# STM32.net
KiCad netlist of a schematic drawn in Altium Designer
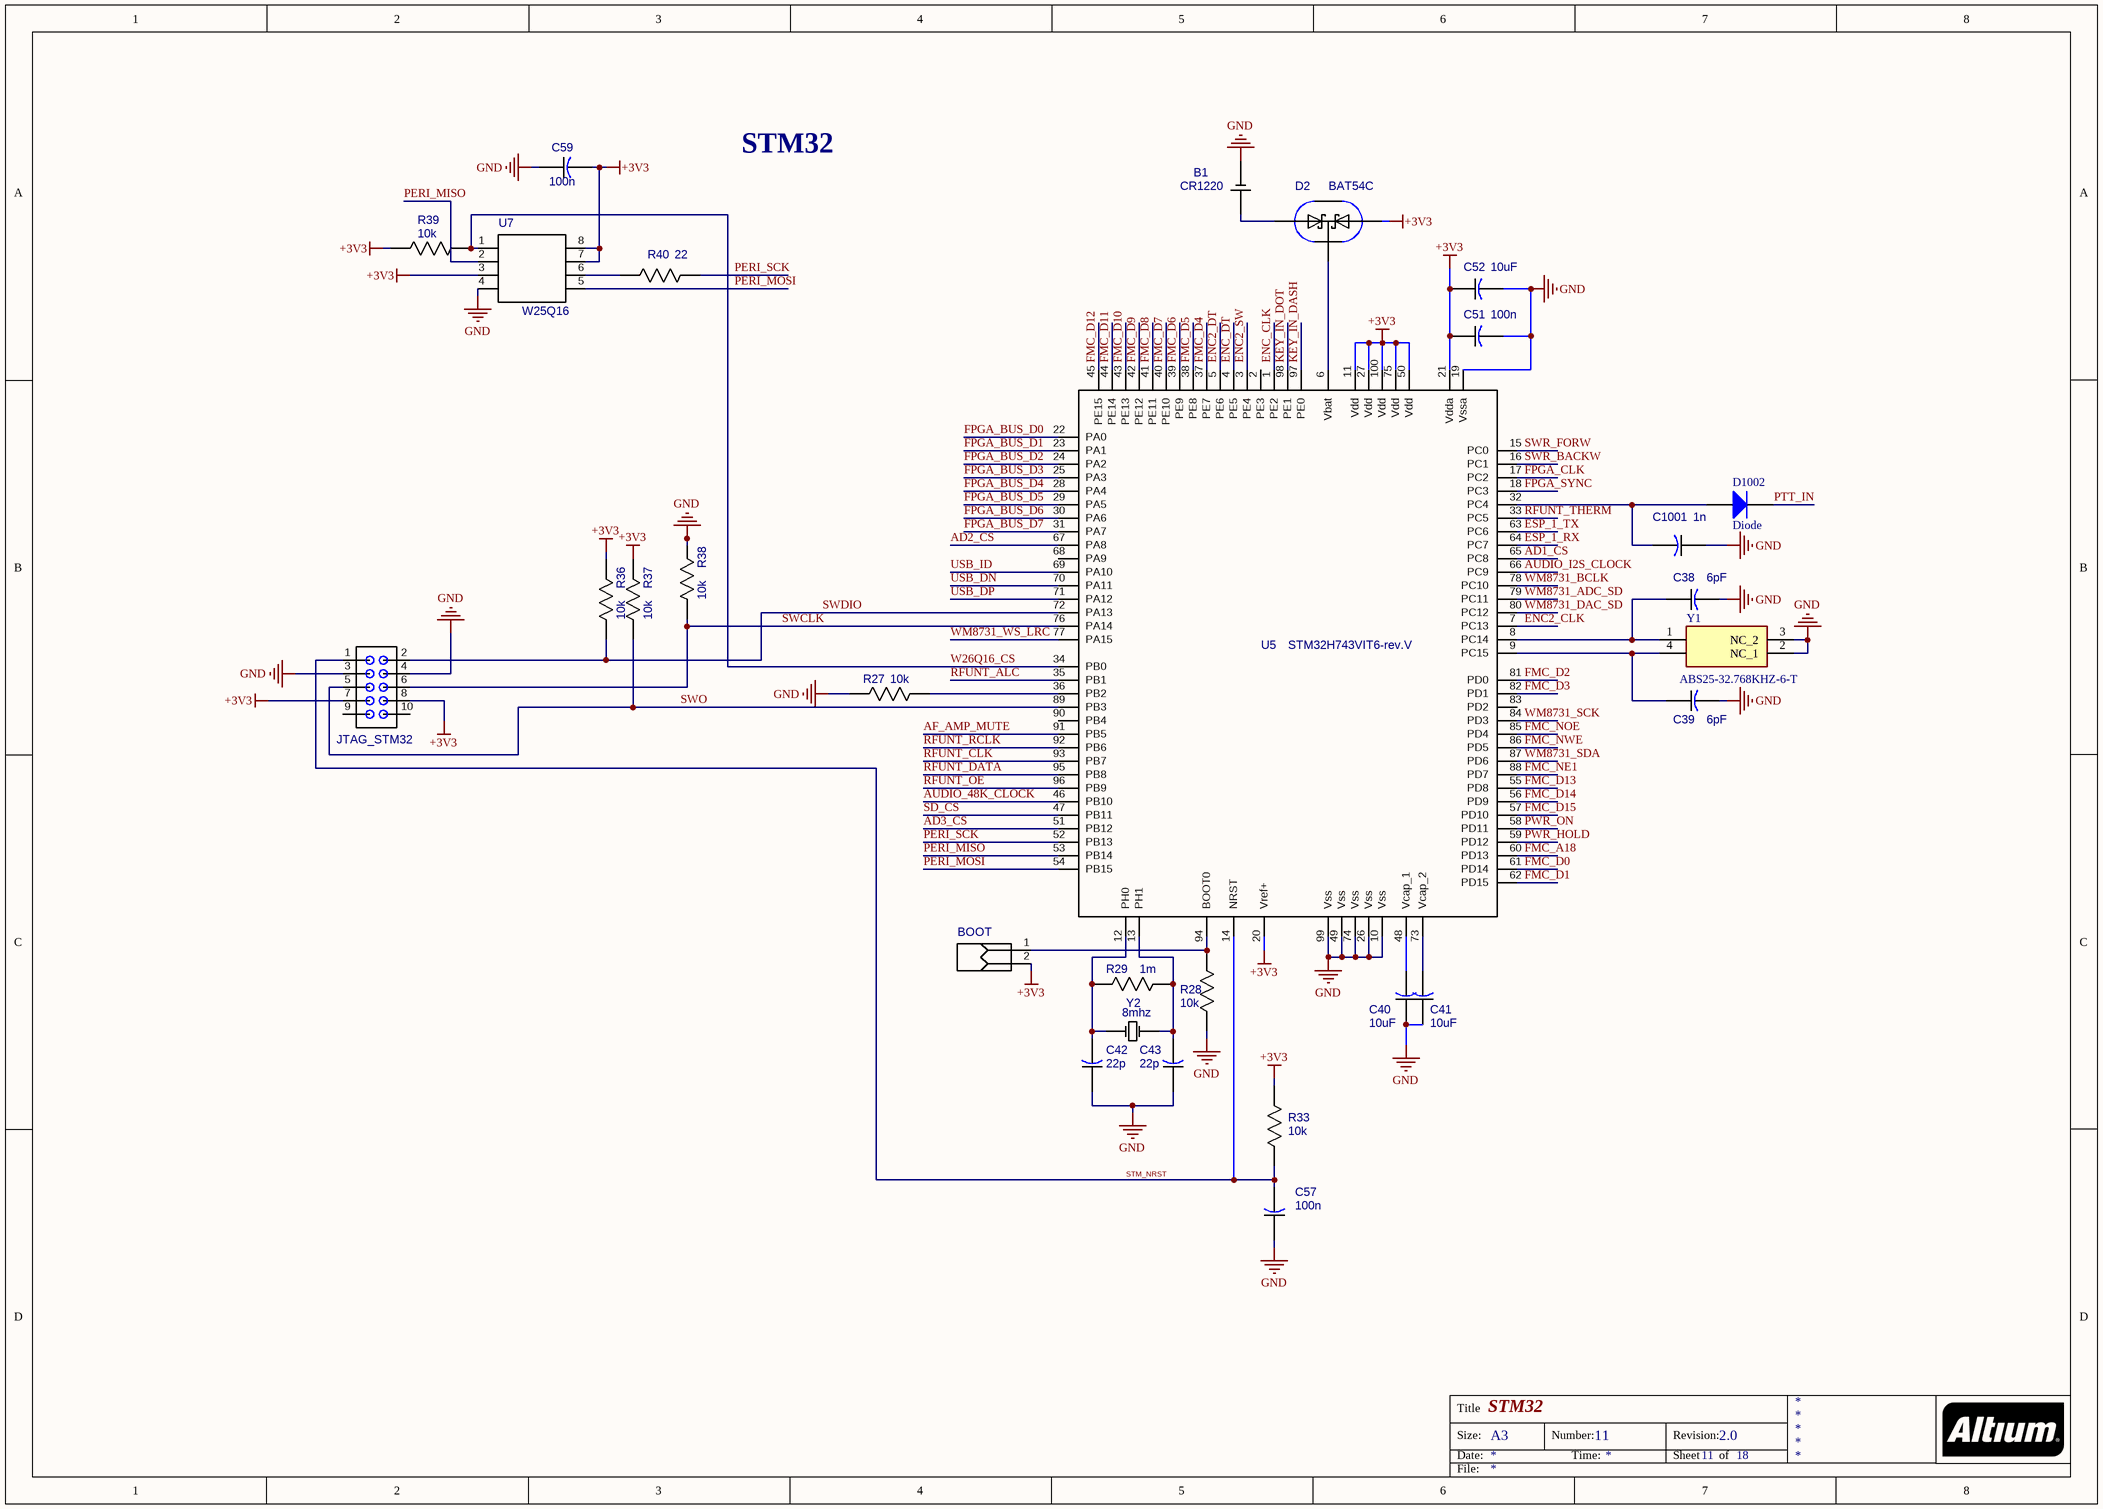
[diagram p0: STM32.SchDoc]

(export (version "E")
  (design (tool "Eeschema 10.0.6"))
  (components
    (comp (ref "B1")
      (value "CR1220")
      (footprint "KLS5-CR1220-01")
      (description "BR1632A/FA")
      (fields (field (name "Comment") "CR1220 +"))
      (libsource (lib "*") (part "BR1632A/FA"))
    )
    (comp (ref "BOOT")
      (value "~")
      (footprint "51022-0200")
      (description "2 Pin")
      (libsource (lib "*") (part "51022-0200"))
    )
    (comp (ref "C38")
      (value "6pF")
      (footprint "CAP_0805")
      (description "CAP_0805")
      (libsource (lib "*") (part "CAP_0805"))
    )
    (comp (ref "C39")
      (value "6pF")
      (footprint "CAP_0805")
      (description "CAP_0805")
      (libsource (lib "*") (part "CAP_0805"))
    )
    (comp (ref "C40")
      (value "10uF")
      (footprint "CAP_0805")
      (description "CAP_0805")
      (libsource (lib "*") (part "CAP_0805"))
    )
    (comp (ref "C41")
      (value "10uF")
      (footprint "CAP_0805")
      (description "CAP_0805")
      (libsource (lib "*") (part "CAP_0805"))
    )
    (comp (ref "C42")
      (value "22p")
      (footprint "CAP_0805")
      (description "CAP_0805")
      (libsource (lib "*") (part "CAP_0805"))
    )
    (comp (ref "C43")
      (value "22p")
      (footprint "CAP_0805")
      (description "CAP_0805")
      (libsource (lib "*") (part "CAP_0805"))
    )
    (comp (ref "C51")
      (value "100n")
      (footprint "CAP_0805")
      (description "CAP_0805")
      (libsource (lib "*") (part "CAP_0805"))
    )
    (comp (ref "C52")
      (value "10uF")
      (footprint "CAP_0805")
      (description "CAP_0805")
      (libsource (lib "*") (part "CAP_0805"))
    )
    (comp (ref "C57")
      (value "100n")
      (footprint "CAP_0805")
      (description "CAP_0805")
      (libsource (lib "*") (part "CAP_0805"))
    )
    (comp (ref "C59")
      (value "100n")
      (footprint "CAP_0805")
      (description "CAP_0805")
      (libsource (lib "*") (part "CAP_0805"))
    )
    (comp (ref "C1001")
      (value "1n")
      (footprint "CAP_0805")
      (description "CAP_0805")
      (fields (field (name "Comment") "100n"))
      (libsource (lib "*") (part "CAP_0805"))
    )
    (comp (ref "D2") (value "BAT54C") (footprint "BAT54C") (libsource (lib "*") (part "BAT54C")))
    (comp (ref "D1002")
      (value "Diode")
      (footprint "C1206")
      (description "Default Diode")
      (fields (field (name "PUBLISHER") "Altium Limited"))
      (libsource (lib "Miscellaneous Devices") (part "Diode"))
    )
    (comp (ref "JTAG_STM32")
      (value "~")
      (footprint "IDC10")
      (description "2*5 Pin")
      (libsource (lib "*") (part "IDC10"))
    )
    (comp (ref "R27")
      (value "10k")
      (footprint "RES_0805")
      (description "RES_0805")
      (libsource (lib "*") (part "RES_0805"))
    )
    (comp (ref "R28")
      (value "10k")
      (footprint "RES_0805")
      (description "RES_0805")
      (libsource (lib "*") (part "RES_0805"))
    )
    (comp (ref "R29")
      (value "1m")
      (footprint "RES_0805")
      (description "RES_0805")
      (libsource (lib "*") (part "RES_0805"))
    )
    (comp (ref "R33")
      (value "10k")
      (footprint "RES_0805")
      (description "RES_0805")
      (libsource (lib "*") (part "RES_0805"))
    )
    (comp (ref "R36")
      (value "10k")
      (footprint "RES_0805")
      (description "RES_0805")
      (libsource (lib "*") (part "RES_0805"))
    )
    (comp (ref "R37")
      (value "10k")
      (footprint "RES_0805")
      (description "RES_0805")
      (libsource (lib "*") (part "RES_0805"))
    )
    (comp (ref "R38")
      (value "10k")
      (footprint "RES_0805")
      (description "RES_0805")
      (libsource (lib "*") (part "RES_0805"))
    )
    (comp (ref "R39")
      (value "10k")
      (footprint "RES_0805")
      (description "RES_0805")
      (libsource (lib "*") (part "RES_0805"))
    )
    (comp (ref "R40")
      (value "22")
      (footprint "RES_0805")
      (description "RES_0805")
      (libsource (lib "*") (part "RES_0805"))
    )
    (comp (ref "U5")
      (value "STM32H743VIT6-rev.V")
      (footprint "STM32H743VIT6")
      (description "STM32H743VIT6")
      (libsource (lib "*") (part "STM32H743VIT6"))
    )
    (comp (ref "U7") (value "W25Q16") (footprint "W25Q16") (libsource (lib "*") (part "W25Q16")))
    (comp (ref "Y1")
      (value "ABS25-32.768KHZ-6-T")
      (footprint "SamacSys:ABS25")
      (description "Crystal or Oscillator")
      (fields
        (field (name "MOUSER PART NUMBER") "815-ABS25-32.768K6-T")
        (field (name "RS PART NUMBER") "1712795P")
      )
      (libsource (lib "*") (part "ABS25-32.768KHZ-6-T"))
    )
    (comp (ref "Y2")
      (value "8mhz")
      (footprint "ECS-200-20-1")
      (description "ECS-200-20-1")
      (libsource (lib "*") (part "ECS-200-20-1"))
    )
  )
  (nets
    (net (code "1") (name "+3V3") (class "Default")
      (node (ref "BOOT") (pin "2") (pinfunction "2_2") (pintype "passive"))
      (node (ref "C51") (pin "1") (pinfunction "1_1") (pintype "passive"))
      (node (ref "C52") (pin "1") (pinfunction "1_1") (pintype "passive"))
      (node (ref "C59") (pin "2") (pinfunction "2_2") (pintype "passive"))
      (node (ref "D2") (pin "1") (pinfunction "(A1)_1") (pintype "passive"))
      (node (ref "JTAG_STM32") (pin "7") (pinfunction "7_7") (pintype "passive"))
      (node (ref "JTAG_STM32") (pin "8") (pinfunction "8_8") (pintype "passive"))
      (node (ref "R33") (pin "2") (pinfunction "2_2") (pintype "passive"))
      (node (ref "R36") (pin "1") (pinfunction "1_1") (pintype "passive"))
      (node (ref "R37") (pin "1") (pinfunction "1_1") (pintype "passive"))
      (node (ref "R39") (pin "1") (pinfunction "1_1") (pintype "passive"))
      (node (ref "U5") (pin "100") (pinfunction "Vdd_100") (pintype "passive"))
      (node (ref "U5") (pin "11") (pinfunction "Vdd_11") (pintype "passive"))
      (node (ref "U5") (pin "20") (pinfunction "Vref+_20") (pintype "passive"))
      (node (ref "U5") (pin "21") (pinfunction "Vdda_21") (pintype "passive"))
      (node (ref "U5") (pin "27") (pinfunction "Vdd_27") (pintype "passive"))
      (node (ref "U5") (pin "50") (pinfunction "Vdd_50") (pintype "passive"))
      (node (ref "U5") (pin "75") (pinfunction "Vdd_75") (pintype "passive"))
      (node (ref "U7") (pin "3") (pinfunction "WP_3") (pintype "passive"))
      (node (ref "U7") (pin "7") (pinfunction "HOLD_7") (pintype "passive"))
      (node (ref "U7") (pin "8") (pinfunction "VCC_8") (pintype "passive"))
    )
    (net (code "2") (name "/AD1_CS") (class "Default")
      (node (ref "U5") (pin "65") (pinfunction "PC8_65") (pintype "passive"))
    )
    (net (code "3") (name "/AD2_CS") (class "Default")
      (node (ref "U5") (pin "67") (pinfunction "PA8_67") (pintype "passive"))
    )
    (net (code "4") (name "/AD3_CS") (class "Default")
      (node (ref "U5") (pin "51") (pinfunction "PB12_51") (pintype "passive"))
    )
    (net (code "5") (name "/AF_AMP_MUTE") (class "Default")
      (node (ref "U5") (pin "91") (pinfunction "PB5_91") (pintype "passive"))
    )
    (net (code "6") (name "/AUDIO_48K_CLOCK") (class "Default")
      (node (ref "U5") (pin "46") (pinfunction "PB10_46") (pintype "passive"))
    )
    (net (code "7") (name "/AUDIO_I2S_CLOCK") (class "Default")
      (node (ref "U5") (pin "66") (pinfunction "PC9_66") (pintype "passive"))
    )
    (net (code "8") (name "/ENC2_CLK") (class "Default")
      (node (ref "U5") (pin "7") (pinfunction "PC13_7") (pintype "passive"))
    )
    (net (code "9") (name "/ENC2_DT") (class "Default")
      (node (ref "U5") (pin "5") (pinfunction "PE6_5") (pintype "passive"))
    )
    (net (code "10") (name "/ENC2_SW") (class "Default")
      (node (ref "U5") (pin "3") (pinfunction "PE4_3") (pintype "passive"))
    )
    (net (code "11") (name "/ENC_CLK") (class "Default")
      (node (ref "U5") (pin "1") (pinfunction "PE2_1") (pintype "passive"))
    )
    (net (code "12") (name "/ENC_DT") (class "Default")
      (node (ref "U5") (pin "4") (pinfunction "PE5_4") (pintype "passive"))
    )
    (net (code "13") (name "/ESP_1_RX") (class "Default")
      (node (ref "U5") (pin "64") (pinfunction "PC7_64") (pintype "passive"))
    )
    (net (code "14") (name "/ESP_1_TX") (class "Default")
      (node (ref "U5") (pin "63") (pinfunction "PC6_63") (pintype "passive"))
    )
    (net (code "15") (name "/FMC_A18") (class "Default")
      (node (ref "U5") (pin "60") (pinfunction "PD13_60") (pintype "passive"))
    )
    (net (code "16") (name "/FMC_D0") (class "Default")
      (node (ref "U5") (pin "61") (pinfunction "PD14_61") (pintype "passive"))
    )
    (net (code "17") (name "/FMC_D1") (class "Default")
      (node (ref "U5") (pin "62") (pinfunction "PD15_62") (pintype "passive"))
    )
    (net (code "18") (name "/FMC_D2") (class "Default")
      (node (ref "U5") (pin "81") (pinfunction "PD0_81") (pintype "passive"))
    )
    (net (code "19") (name "/FMC_D3") (class "Default")
      (node (ref "U5") (pin "82") (pinfunction "PD1_82") (pintype "passive"))
    )
    (net (code "20") (name "/FMC_D4") (class "Default")
      (node (ref "U5") (pin "37") (pinfunction "PE7_37") (pintype "passive"))
    )
    (net (code "21") (name "/FMC_D5") (class "Default")
      (node (ref "U5") (pin "38") (pinfunction "PE8_38") (pintype "passive"))
    )
    (net (code "22") (name "/FMC_D6") (class "Default")
      (node (ref "U5") (pin "39") (pinfunction "PE9_39") (pintype "passive"))
    )
    (net (code "23") (name "/FMC_D7") (class "Default")
      (node (ref "U5") (pin "40") (pinfunction "PE10_40") (pintype "passive"))
    )
    (net (code "24") (name "/FMC_D8") (class "Default")
      (node (ref "U5") (pin "41") (pinfunction "PE11_41") (pintype "passive"))
    )
    (net (code "25") (name "/FMC_D9") (class "Default")
      (node (ref "U5") (pin "42") (pinfunction "PE12_42") (pintype "passive"))
    )
    (net (code "26") (name "/FMC_D10") (class "Default")
      (node (ref "U5") (pin "43") (pinfunction "PE13_43") (pintype "passive"))
    )
    (net (code "27") (name "/FMC_D11") (class "Default")
      (node (ref "U5") (pin "44") (pinfunction "PE14_44") (pintype "passive"))
    )
    (net (code "28") (name "/FMC_D12") (class "Default")
      (node (ref "U5") (pin "45") (pinfunction "PE15_45") (pintype "passive"))
    )
    (net (code "29") (name "/FMC_D13") (class "Default")
      (node (ref "U5") (pin "55") (pinfunction "PD8_55") (pintype "passive"))
    )
    (net (code "30") (name "/FMC_D14") (class "Default")
      (node (ref "U5") (pin "56") (pinfunction "PD9_56") (pintype "passive"))
    )
    (net (code "31") (name "/FMC_D15") (class "Default")
      (node (ref "U5") (pin "57") (pinfunction "PD10_57") (pintype "passive"))
    )
    (net (code "32") (name "/FMC_NE1") (class "Default")
      (node (ref "U5") (pin "88") (pinfunction "PD7_88") (pintype "passive"))
    )
    (net (code "33") (name "/FMC_NOE") (class "Default")
      (node (ref "U5") (pin "85") (pinfunction "PD4_85") (pintype "passive"))
    )
    (net (code "34") (name "/FMC_NWE") (class "Default")
      (node (ref "U5") (pin "86") (pinfunction "PD5_86") (pintype "passive"))
    )
    (net (code "35") (name "/FPGA_BUS_D0") (class "Default")
      (node (ref "U5") (pin "22") (pinfunction "PA0_22") (pintype "passive"))
    )
    (net (code "36") (name "/FPGA_BUS_D1") (class "Default")
      (node (ref "U5") (pin "23") (pinfunction "PA1_23") (pintype "passive"))
    )
    (net (code "37") (name "/FPGA_BUS_D2") (class "Default")
      (node (ref "U5") (pin "24") (pinfunction "PA2_24") (pintype "passive"))
    )
    (net (code "38") (name "/FPGA_BUS_D3") (class "Default")
      (node (ref "U5") (pin "25") (pinfunction "PA3_25") (pintype "passive"))
    )
    (net (code "39") (name "/FPGA_BUS_D4") (class "Default")
      (node (ref "U5") (pin "28") (pinfunction "PA4_28") (pintype "passive"))
    )
    (net (code "40") (name "/FPGA_BUS_D5") (class "Default")
      (node (ref "U5") (pin "29") (pinfunction "PA5_29") (pintype "passive"))
    )
    (net (code "41") (name "/FPGA_BUS_D6") (class "Default")
      (node (ref "U5") (pin "30") (pinfunction "PA6_30") (pintype "passive"))
    )
    (net (code "42") (name "/FPGA_BUS_D7") (class "Default")
      (node (ref "U5") (pin "31") (pinfunction "PA7_31") (pintype "passive"))
    )
    (net (code "43") (name "/FPGA_CLK") (class "Default")
      (node (ref "U5") (pin "17") (pinfunction "PC2_17") (pintype "passive"))
    )
    (net (code "44") (name "/FPGA_SYNC") (class "Default")
      (node (ref "U5") (pin "18") (pinfunction "PC3_18") (pintype "passive"))
    )
    (net (code "45") (name "/KEY_IN_DASH") (class "Default")
      (node (ref "U5") (pin "97") (pinfunction "PE0_97") (pintype "passive"))
    )
    (net (code "46") (name "/KEY_IN_DOT") (class "Default")
      (node (ref "U5") (pin "98") (pinfunction "PE1_98") (pintype "passive"))
    )
    (net (code "47") (name "/PERI_MISO") (class "Default")
      (node (ref "U5") (pin "53") (pinfunction "PB14_53") (pintype "passive"))
      (node (ref "U7") (pin "2") (pinfunction "SO_2") (pintype "passive"))
    )
    (net (code "48") (name "/PERI_MOSI") (class "Default")
      (node (ref "U5") (pin "54") (pinfunction "PB15_54") (pintype "passive"))
      (node (ref "U7") (pin "5") (pinfunction "SI_5") (pintype "passive"))
    )
    (net (code "49") (name "/PERI_SCK") (class "Default")
      (node (ref "R40") (pin "2") (pinfunction "2_2") (pintype "passive"))
      (node (ref "U5") (pin "52") (pinfunction "PB13_52") (pintype "passive"))
    )
    (net (code "50") (name "/PTT_IN") (class "Default")
      (node (ref "D1002") (pin "2") (pinfunction "K_2") (pintype "passive"))
    )
    (net (code "51") (name "/PWR_HOLD") (class "Default")
      (node (ref "U5") (pin "59") (pinfunction "PD12_59") (pintype "passive"))
    )
    (net (code "52") (name "/PWR_ON") (class "Default")
      (node (ref "U5") (pin "58") (pinfunction "PD11_58") (pintype "passive"))
    )
    (net (code "53") (name "/RFUNT_ALC") (class "Default")
      (node (ref "U5") (pin "35") (pinfunction "PB1_35") (pintype "passive"))
    )
    (net (code "54") (name "/RFUNT_CLK") (class "Default")
      (node (ref "U5") (pin "93") (pinfunction "PB7_93") (pintype "passive"))
    )
    (net (code "55") (name "/RFUNT_DATA") (class "Default")
      (node (ref "U5") (pin "95") (pinfunction "PB8_95") (pintype "passive"))
    )
    (net (code "56") (name "/RFUNT_OE") (class "Default")
      (node (ref "U5") (pin "96") (pinfunction "PB9_96") (pintype "passive"))
    )
    (net (code "57") (name "/RFUNT_RCLK") (class "Default")
      (node (ref "U5") (pin "92") (pinfunction "PB6_92") (pintype "passive"))
    )
    (net (code "58") (name "/RFUNT_THERM") (class "Default")
      (node (ref "U5") (pin "33") (pinfunction "PC5_33") (pintype "passive"))
    )
    (net (code "59") (name "/SD_CS") (class "Default")
      (node (ref "U5") (pin "47") (pinfunction "PB11_47") (pintype "passive"))
    )
    (net (code "60") (name "/STM_NRST") (class "Default")
      (node (ref "C57") (pin "2") (pinfunction "2_2") (pintype "passive"))
      (node (ref "JTAG_STM32") (pin "1") (pinfunction "1_1") (pintype "passive"))
      (node (ref "R33") (pin "1") (pinfunction "1_1") (pintype "passive"))
      (node (ref "U5") (pin "14") (pinfunction "NRST_14") (pintype "passive"))
    )
    (net (code "61") (name "/SWCLK") (class "Default")
      (node (ref "JTAG_STM32") (pin "6") (pinfunction "6_6") (pintype "passive"))
      (node (ref "R38") (pin "2") (pinfunction "2_2") (pintype "passive"))
      (node (ref "U5") (pin "76") (pinfunction "PA14_76") (pintype "passive"))
    )
    (net (code "62") (name "/SWDIO") (class "Default")
      (node (ref "JTAG_STM32") (pin "2") (pinfunction "2_2") (pintype "passive"))
      (node (ref "R36") (pin "2") (pinfunction "2_2") (pintype "passive"))
      (node (ref "U5") (pin "72") (pinfunction "PA13_72") (pintype "passive"))
    )
    (net (code "63") (name "/SWO") (class "Default")
      (node (ref "JTAG_STM32") (pin "5") (pinfunction "5_5") (pintype "passive"))
      (node (ref "R37") (pin "2") (pinfunction "2_2") (pintype "passive"))
      (node (ref "U5") (pin "89") (pinfunction "PB3_89") (pintype "passive"))
    )
    (net (code "64") (name "/SWR_BACKW") (class "Default")
      (node (ref "U5") (pin "16") (pinfunction "PC1_16") (pintype "passive"))
    )
    (net (code "65") (name "/SWR_FORW") (class "Default")
      (node (ref "U5") (pin "15") (pinfunction "PC0_15") (pintype "passive"))
    )
    (net (code "66") (name "/USB_DN") (class "Default")
      (node (ref "U5") (pin "70") (pinfunction "PA11_70") (pintype "passive"))
    )
    (net (code "67") (name "/USB_DP") (class "Default")
      (node (ref "U5") (pin "71") (pinfunction "PA12_71") (pintype "passive"))
    )
    (net (code "68") (name "/USB_ID") (class "Default")
      (node (ref "U5") (pin "69") (pinfunction "PA10_69") (pintype "passive"))
    )
    (net (code "69") (name "/W26Q16_CS") (class "Default")
      (node (ref "R39") (pin "2") (pinfunction "2_2") (pintype "passive"))
      (node (ref "U5") (pin "34") (pinfunction "PB0_34") (pintype "passive"))
      (node (ref "U7") (pin "1") (pinfunction "CS_1") (pintype "passive"))
    )
    (net (code "70") (name "/WM8731_ADC_SD") (class "Default")
      (node (ref "U5") (pin "79") (pinfunction "PC11_79") (pintype "passive"))
    )
    (net (code "71") (name "/WM8731_BCLK") (class "Default")
      (node (ref "U5") (pin "78") (pinfunction "PC10_78") (pintype "passive"))
    )
    (net (code "72") (name "/WM8731_DAC_SD") (class "Default")
      (node (ref "U5") (pin "80") (pinfunction "PC12_80") (pintype "passive"))
    )
    (net (code "73") (name "/WM8731_SCK") (class "Default")
      (node (ref "U5") (pin "84") (pinfunction "PD3_84") (pintype "passive"))
    )
    (net (code "74") (name "/WM8731_SDA") (class "Default")
      (node (ref "U5") (pin "87") (pinfunction "PD6_87") (pintype "passive"))
    )
    (net (code "75") (name "/WM8731_WS_LRC") (class "Default")
      (node (ref "U5") (pin "77") (pinfunction "PA15_77") (pintype "passive"))
    )
    (net (code "76") (name "GND") (class "Default")
      (node (ref "B1") (pin "2") (pinfunction "NEG_2") (pintype "passive"))
      (node (ref "C1001") (pin "1") (pinfunction "1_1") (pintype "passive"))
      (node (ref "C38") (pin "2") (pinfunction "2_2") (pintype "passive"))
      (node (ref "C39") (pin "2") (pinfunction "2_2") (pintype "passive"))
      (node (ref "C40") (pin "1") (pinfunction "1_1") (pintype "passive"))
      (node (ref "C41") (pin "1") (pinfunction "1_1") (pintype "passive"))
      (node (ref "C42") (pin "1") (pinfunction "1_1") (pintype "passive"))
      (node (ref "C43") (pin "1") (pinfunction "1_1") (pintype "passive"))
      (node (ref "C51") (pin "2") (pinfunction "2_2") (pintype "passive"))
      (node (ref "C52") (pin "2") (pinfunction "2_2") (pintype "passive"))
      (node (ref "C57") (pin "1") (pinfunction "1_1") (pintype "passive"))
      (node (ref "C59") (pin "1") (pinfunction "1_1") (pintype "passive"))
      (node (ref "JTAG_STM32") (pin "3") (pinfunction "3_3") (pintype "passive"))
      (node (ref "JTAG_STM32") (pin "4") (pinfunction "4_4") (pintype "passive"))
      (node (ref "R27") (pin "1") (pinfunction "1_1") (pintype "passive"))
      (node (ref "R28") (pin "1") (pinfunction "1_1") (pintype "passive"))
      (node (ref "R38") (pin "1") (pinfunction "1_1") (pintype "passive"))
      (node (ref "U5") (pin "10") (pinfunction "Vss_10") (pintype "passive"))
      (node (ref "U5") (pin "19") (pinfunction "Vssa_19") (pintype "passive"))
      (node (ref "U5") (pin "26") (pinfunction "Vss_26") (pintype "passive"))
      (node (ref "U5") (pin "49") (pinfunction "Vss_49") (pintype "passive"))
      (node (ref "U5") (pin "74") (pinfunction "Vss_74") (pintype "passive"))
      (node (ref "U5") (pin "99") (pinfunction "Vss_99") (pintype "passive"))
      (node (ref "U7") (pin "4") (pinfunction "GND_4") (pintype "passive"))
      (node (ref "Y1") (pin "2") (pinfunction "NC_1_2") (pintype "passive"))
      (node (ref "Y1") (pin "3") (pinfunction "NC_2_3") (pintype "passive"))
    )
    (net (code "77") (name "Net-(B1-POS)") (class "Default")
      (node (ref "B1") (pin "1") (pinfunction "POS_1") (pintype "passive"))
      (node (ref "D2") (pin "2") (pinfunction "(A2)_2") (pintype "passive"))
    )
    (net (code "78") (name "Net-(D2-(K1),(K2))") (class "Default")
      (node (ref "D2") (pin "3") (pinfunction "(K1),(K2)_3") (pintype "passive"))
      (node (ref "U5") (pin "6") (pinfunction "Vbat_6") (pintype "passive"))
    )
    (net (code "79") (name "Net-(D1002-A)") (class "Default")
      (node (ref "C1001") (pin "2") (pinfunction "2_2") (pintype "passive"))
      (node (ref "D1002") (pin "1") (pinfunction "A_1") (pintype "passive"))
      (node (ref "U5") (pin "32") (pinfunction "PC4_32") (pintype "passive"))
    )
    (net (code "80") (name "Net-(U5-BOOT0)") (class "Default")
      (node (ref "BOOT") (pin "1") (pinfunction "1_1") (pintype "passive"))
      (node (ref "R28") (pin "2") (pinfunction "2_2") (pintype "passive"))
      (node (ref "U5") (pin "94") (pinfunction "BOOT0_94") (pintype "passive"))
    )
    (net (code "81") (name "Net-(U5-PB2)") (class "Default")
      (node (ref "R27") (pin "2") (pinfunction "2_2") (pintype "passive"))
      (node (ref "U5") (pin "36") (pinfunction "PB2_36") (pintype "passive"))
    )
    (net (code "82") (name "Net-(U5-PC14)") (class "Default")
      (node (ref "C38") (pin "1") (pinfunction "1_1") (pintype "passive"))
      (node (ref "U5") (pin "8") (pinfunction "PC14_8") (pintype "passive"))
      (node (ref "Y1") (pin "1") (pinfunction "1_1") (pintype "passive"))
    )
    (net (code "83") (name "Net-(U5-PC15)") (class "Default")
      (node (ref "C39") (pin "1") (pinfunction "1_1") (pintype "passive"))
      (node (ref "U5") (pin "9") (pinfunction "PC15_9") (pintype "passive"))
      (node (ref "Y1") (pin "4") (pinfunction "4_4") (pintype "passive"))
    )
    (net (code "84") (name "Net-(U5-PH0)") (class "Default")
      (node (ref "C42") (pin "2") (pinfunction "2_2") (pintype "passive"))
      (node (ref "R29") (pin "1") (pinfunction "1_1") (pintype "passive"))
      (node (ref "U5") (pin "12") (pinfunction "PH0_12") (pintype "passive"))
      (node (ref "Y2") (pin "1") (pinfunction "OSC1_1") (pintype "passive"))
    )
    (net (code "85") (name "Net-(U5-PH1)") (class "Default")
      (node (ref "C43") (pin "2") (pinfunction "2_2") (pintype "passive"))
      (node (ref "R29") (pin "2") (pinfunction "2_2") (pintype "passive"))
      (node (ref "U5") (pin "13") (pinfunction "PH1_13") (pintype "passive"))
      (node (ref "Y2") (pin "2") (pinfunction "OSC2_2") (pintype "passive"))
    )
    (net (code "86") (name "Net-(U5-Vcap_1)") (class "Default")
      (node (ref "C40") (pin "2") (pinfunction "2_2") (pintype "passive"))
      (node (ref "U5") (pin "48") (pinfunction "Vcap_1_48") (pintype "passive"))
    )
    (net (code "87") (name "Net-(U5-Vcap_2)") (class "Default")
      (node (ref "C41") (pin "2") (pinfunction "2_2") (pintype "passive"))
      (node (ref "U5") (pin "73") (pinfunction "Vcap_2_73") (pintype "passive"))
    )
    (net (code "88") (name "Net-(U7-CLK)") (class "Default")
      (node (ref "R40") (pin "1") (pinfunction "1_1") (pintype "passive"))
      (node (ref "U7") (pin "6") (pinfunction "CLK_6") (pintype "passive"))
    )
    (net (code "89") (name "unconnected-(JTAG_STM32-Pad9)") (class "Default")
      (node (ref "JTAG_STM32") (pin "9") (pinfunction "9_9") (pintype "passive"))
    )
    (net (code "90") (name "unconnected-(JTAG_STM32-Pad10)") (class "Default")
      (node (ref "JTAG_STM32") (pin "10") (pinfunction "10_10") (pintype "passive"))
    )
    (net (code "91") (name "unconnected-(U5-PA9-Pad68)") (class "Default")
      (node (ref "U5") (pin "68") (pinfunction "PA9_68") (pintype "passive"))
    )
    (net (code "92") (name "unconnected-(U5-PB4-Pad90)") (class "Default")
      (node (ref "U5") (pin "90") (pinfunction "PB4_90") (pintype "passive"))
    )
    (net (code "93") (name "unconnected-(U5-PD2-Pad83)") (class "Default")
      (node (ref "U5") (pin "83") (pinfunction "PD2_83") (pintype "passive"))
    )
    (net (code "94") (name "unconnected-(U5-PE3-Pad2)") (class "Default")
      (node (ref "U5") (pin "2") (pinfunction "PE3_2") (pintype "passive"))
    )
  )
)
